# fpga-bank8.net
KiCad netlist of a schematic drawn in Altium Designer
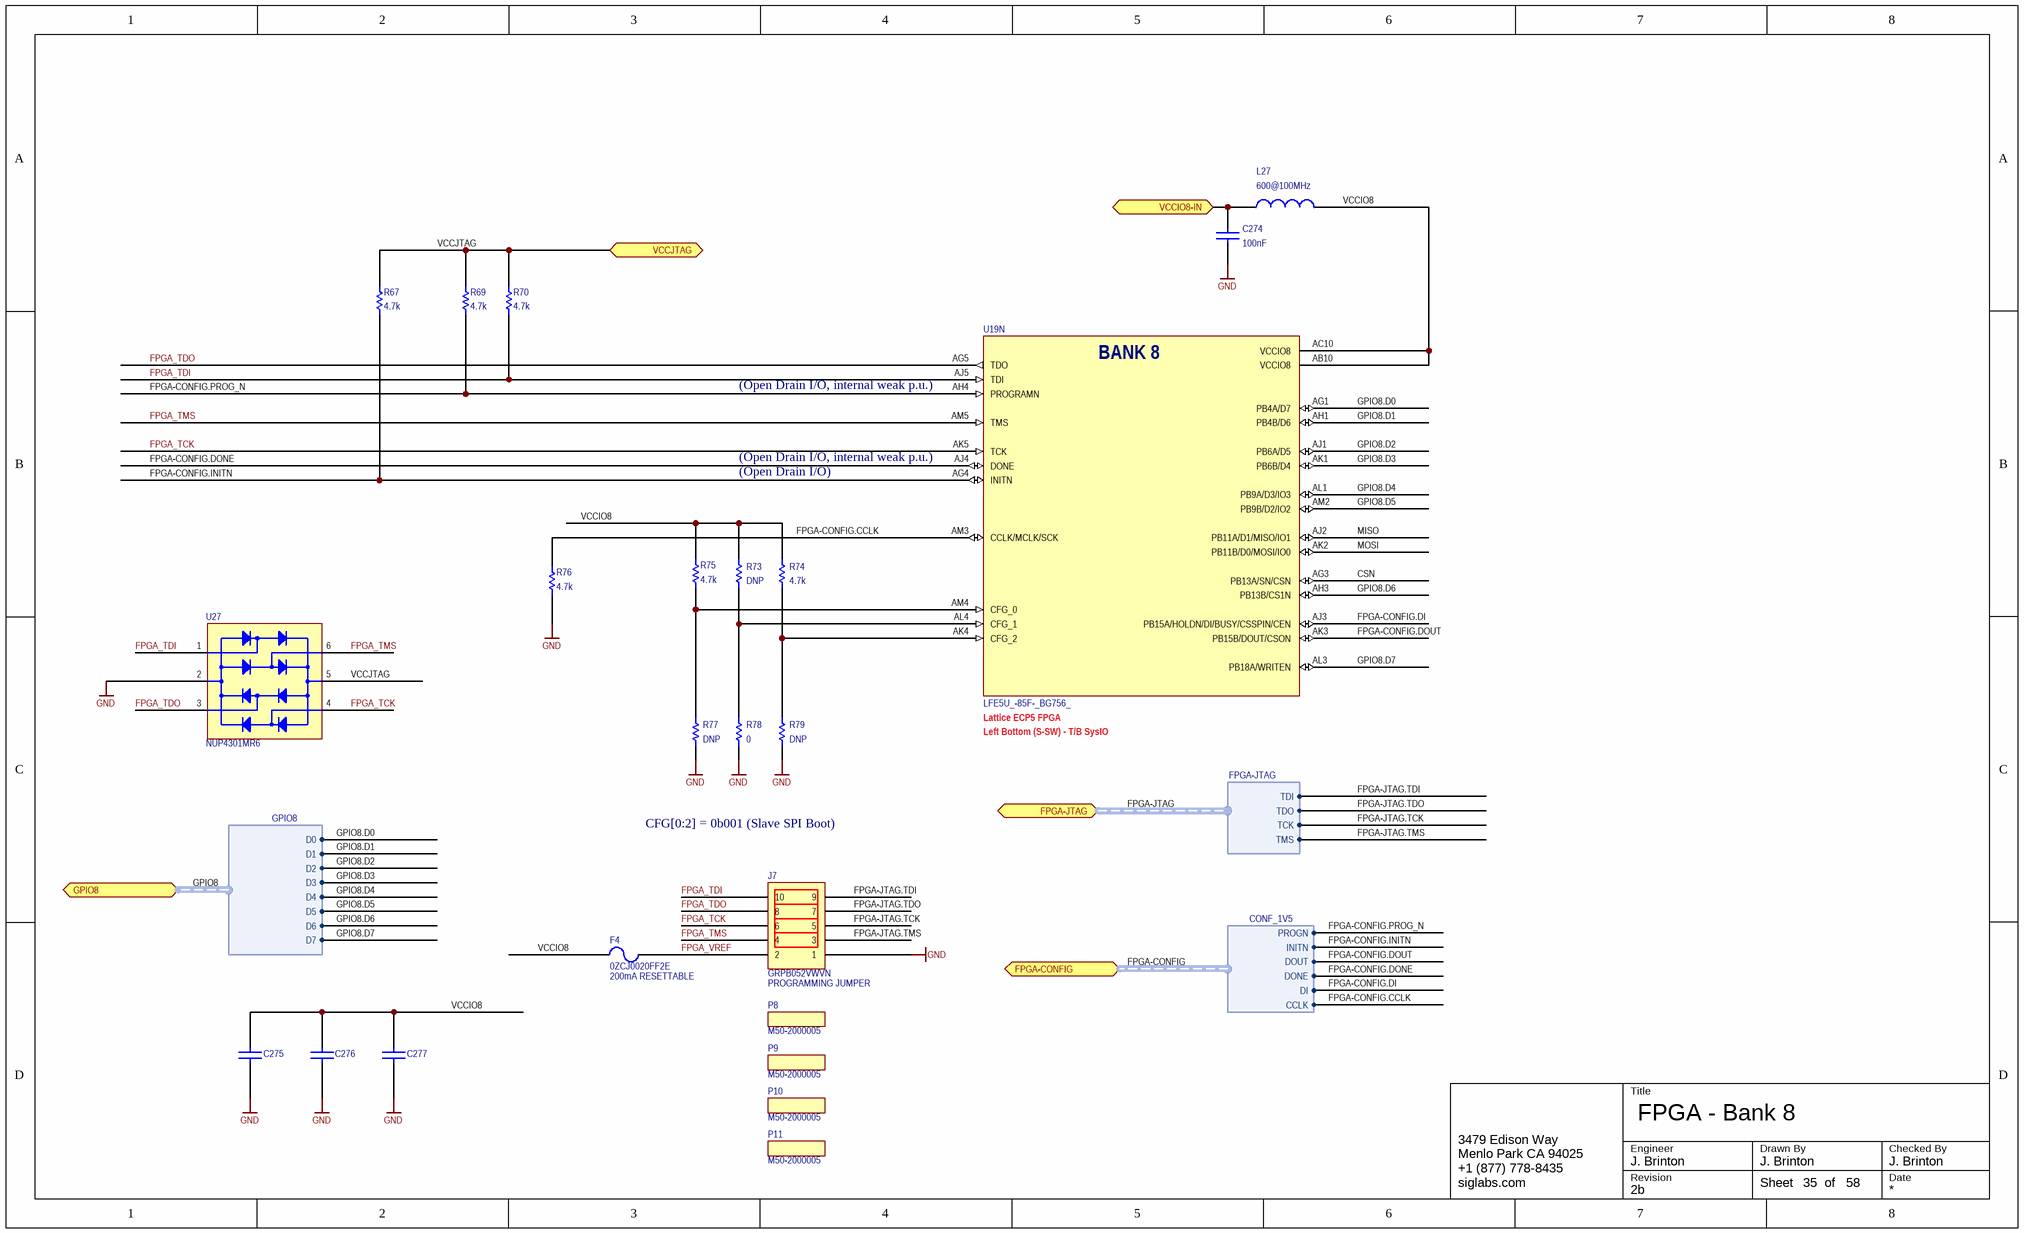
[diagram p0: fpga-bank8.SchDoc]

(export (version "E")
  (design (tool "Eeschema 10.0.6"))
  (components
    (comp (ref "C274")
      (value "100nF")
      (footprint "generic:CAPC1005X56N")
      (description "Ceramic Capacitor 100nF ±10% 16V X7R 0402")
      (fields (field (name "MANUFACTURER") "Murata") (field (name "TOLERANCE") "±10%"))
      (libsource (lib "murata") (part "GRM155R71A104KA01J"))
    )
    (comp (ref "C275")
      (value "GRM21BR71C225KA12L")
      (footprint "generic:CAPC1608X90N")
      (description "Ceramic Capacitor 2.2uF ±10% 10V X7R 0603")
      (fields (field (name "MANUFACTURER") "Murata") (field (name "TOLERANCE") "±10%"))
      (libsource (lib "murata") (part "GRM188R71A225KE15D"))
    )
    (comp (ref "C276")
      (value "GRM155R71C104KA88J")
      (footprint "generic:CAPC1005X56N")
      (description "Ceramic Capacitor 100nF ±10% 16V X7R 0402")
      (fields (field (name "MANUFACTURER") "Murata") (field (name "TOLERANCE") "±10%"))
      (libsource (lib "murata") (part "GRM155R71A104KA01J"))
    )
    (comp (ref "C277")
      (value "GRM155R71C104KA88J")
      (footprint "generic:CAPC1005X56N")
      (description "Ceramic Capacitor 100nF ±10% 16V X7R 0402")
      (fields (field (name "MANUFACTURER") "Murata") (field (name "TOLERANCE") "±10%"))
      (libsource (lib "murata") (part "GRM155R71A104KA01J"))
    )
    (comp (ref "F4")
      (value "0ZCJ0020FF2E")
      (footprint "generic:1206")
      (description "PTC Resettable Fuse, 0.2A, 30V, SMD 1206")
      (fields (field (name "MANUFACTURER") "Bell Fuse"))
      (libsource (lib "bel-fuse") (part "0ZCJ0020FF2E"))
    )
    (comp (ref "J7")
      (value "GRPB052VWVN")
      (footprint "sullins:GRPB052VWVN")
      (description "Male Header, 0.050\" Pitch, 2x5 Position")
      (fields (field (name "MANUFACTURER") "Sullins"))
      (libsource (lib "sullins") (part "GRPB052VWVN"))
    )
    (comp (ref "L27")
      (value "600@100MHz")
      (footprint "0402")
      (description "Ferrite Bead 600-Ohm @ 100MHz 900mA 0402")
      (fields (field (name "MANUFACTURER") "Murata") (field (name "TOLERANCE") "±25%"))
      (libsource (lib "Graviton") (part "IND 0402"))
    )
    (comp (ref "P8")
      (value "M50-2000005")
      (description "1.27mm Jumper Socket")
      (fields (field (name "MANUFACTURER") "Harwin"))
      (libsource (lib "harwin") (part "M50-1900005"))
    )
    (comp (ref "P9")
      (value "M50-2000005")
      (description "1.27mm Jumper Socket")
      (fields (field (name "MANUFACTURER") "Harwin"))
      (libsource (lib "harwin") (part "M50-1900005"))
    )
    (comp (ref "P10")
      (value "M50-2000005")
      (description "1.27mm Jumper Socket")
      (fields (field (name "MANUFACTURER") "Harwin"))
      (libsource (lib "harwin") (part "M50-1900005"))
    )
    (comp (ref "P11")
      (value "M50-2000005")
      (description "1.27mm Jumper Socket")
      (fields (field (name "MANUFACTURER") "Harwin"))
      (libsource (lib "harwin") (part "M50-1900005"))
    )
    (comp (ref "R67")
      (value "4.7k")
      (footprint "generic:0603")
      (description "Thick Film Resistor 4.7k ±1% 0603")
      (fields (field (name "TOLERANCE") "±1%") (field (name "MANUFACTURER") "Panasonic"))
      (libsource (lib "brinton") (part "RES"))
    )
    (comp (ref "R69")
      (value "4.7k")
      (footprint "generic:0603")
      (description "Thick Film Resistor 4.7k ±1% 0603")
      (fields (field (name "TOLERANCE") "±1%") (field (name "MANUFACTURER") "Panasonic"))
      (libsource (lib "brinton") (part "RES"))
    )
    (comp (ref "R70")
      (value "4.7k")
      (footprint "generic:0603")
      (description "Thick Film Resistor 4.7k ±1% 0603")
      (fields (field (name "TOLERANCE") "±1%") (field (name "MANUFACTURER") "Panasonic"))
      (libsource (lib "brinton") (part "RES"))
    )
    (comp (ref "R73")
      (value "ERJ3EKF4701V")
      (footprint "generic:0603")
      (description "Thick Film Resistor 4.7k ±1% 0603")
      (fields
        (field (name "TOLERANCE") "±1%")
        (field (name "MANUFACTURER") "Panasonic")
        (field (name "DO NOT PLACE") "DNP")
      )
      (libsource (lib "brinton") (part "RES"))
    )
    (comp (ref "R74")
      (value "4.7k")
      (footprint "generic:0603")
      (description "Thick Film Resistor 4.7k ±1% 0603")
      (fields (field (name "TOLERANCE") "±1%") (field (name "MANUFACTURER") "Panasonic"))
      (libsource (lib "brinton") (part "RES"))
    )
    (comp (ref "R75")
      (value "4.7k")
      (footprint "generic:0603")
      (description "Thick Film Resistor 4.7k ±1% 0603")
      (fields (field (name "TOLERANCE") "±1%") (field (name "MANUFACTURER") "Panasonic"))
      (libsource (lib "brinton") (part "RES"))
    )
    (comp (ref "R76")
      (value "4.7k")
      (footprint "generic:0603")
      (description "Thick Film Resistor 4.7k ±1% 0603")
      (fields (field (name "TOLERANCE") "±1%") (field (name "MANUFACTURER") "Panasonic"))
      (libsource (lib "brinton") (part "RES"))
    )
    (comp (ref "R77")
      (value "ERJ-3GEY0R00V")
      (footprint "generic:0603")
      (description "Thick Film Resistor Jumper 0603")
      (fields
        (field (name "TOLERANCE") "0")
        (field (name "MANUFACTURER") "Panasonic")
        (field (name "DO NOT PLACE") "DNP")
      )
      (libsource (lib "brinton") (part "RES"))
    )
    (comp (ref "R78")
      (value "0")
      (footprint "generic:0603")
      (description "Thick Film Resistor Jumper 0603")
      (fields (field (name "MANUFACTURER") "Panasonic") (field (name "Comment") "ERJ-3GEY0R00V"))
      (libsource (lib "brinton") (part "RES"))
    )
    (comp (ref "R79")
      (value "ERJ-3GEY0R00V")
      (footprint "generic:0603")
      (description "Thick Film Resistor Jumper 0603")
      (fields
        (field (name "TOLERANCE") "0")
        (field (name "MANUFACTURER") "Panasonic")
        (field (name "DO NOT PLACE") "DNP")
      )
      (libsource (lib "brinton") (part "RES"))
    )
    (comp (ref "U19")
      (value "LFE5U_-85F-_BG756_")
      (footprint "lattice:caBGA756")
      (description "ECP5 FPGA, 85k LUT, 756-caBGA")
      (fields (field (name "MANUFACTURER") "Lattice Semiconductor"))
      (libsource (lib "lattice") (part "LFE5U_-85F-_BG756_"))
    )
    (comp (ref "U27")
      (value "NUP4301MR6")
      (footprint "generic:SOT23-6")
      (description "4-Lane TVS Diode Array")
      (fields (field (name "MANUFACTURER") "On Semiconductor"))
      (libsource (lib "on_semi") (part "NUP4301MR6"))
    )
  )
  (nets
    (net (code "4") (name "/CSN") (class "Default")
      (node (ref "U19") (pin "AG3") (pinfunction "PB13A/SN/CSN_AG3") (pintype "bidirectional"))
    )
    (net (code "5") (name "/FPGA-CONFIG.CCLK") (class "Default")
      (node (ref "R76") (pin "2") (pinfunction "2_2") (pintype "passive"))
      (node (ref "U19") (pin "AM3") (pinfunction "CCLK/MCLK/SCK_AM3") (pintype "bidirectional"))
    )
    (net (code "6") (name "/FPGA-CONFIG.DI") (class "Default")
      (node (ref "U19") (pin "AJ3") (pinfunction "PB15A/HOLDN/DI/BUSY/CSSPIN/CEN_AJ3") (pintype "bidirectional"))
    )
    (net (code "7") (name "/FPGA-CONFIG.DONE") (class "Default")
      (node (ref "U19") (pin "AJ4") (pinfunction "DONE_AJ4") (pintype "bidirectional"))
    )
    (net (code "8") (name "/FPGA-CONFIG.DOUT") (class "Default")
      (node (ref "U19") (pin "AK3") (pinfunction "PB15B/DOUT/CSON_AK3") (pintype "bidirectional"))
    )
    (net (code "9") (name "/FPGA-CONFIG.INITN") (class "Default")
      (node (ref "R67") (pin "1") (pinfunction "1_1") (pintype "passive"))
      (node (ref "U19") (pin "AG4") (pinfunction "INITN_AG4") (pintype "bidirectional"))
    )
    (net (code "10") (name "/FPGA-CONFIG.PROG_N") (class "Default")
      (node (ref "R69") (pin "1") (pinfunction "1_1") (pintype "passive"))
      (node (ref "U19") (pin "AH4") (pinfunction "PROGRAMN_AH4") (pintype "input"))
    )
    (net (code "12") (name "/FPGA-JTAG.TCK") (class "Default")
      (node (ref "J7") (pin "5") (pinfunction "5_5") (pintype "passive"))
    )
    (net (code "13") (name "/FPGA-JTAG.TDI") (class "Default")
      (node (ref "J7") (pin "9") (pinfunction "9_9") (pintype "passive"))
    )
    (net (code "14") (name "/FPGA-JTAG.TDO") (class "Default")
      (node (ref "J7") (pin "7") (pinfunction "7_7") (pintype "passive"))
    )
    (net (code "15") (name "/FPGA-JTAG.TMS") (class "Default")
      (node (ref "J7") (pin "3") (pinfunction "3_3") (pintype "passive"))
    )
    (net (code "17") (name "/FPGA_TCK") (class "Default")
      (node (ref "J7") (pin "6") (pinfunction "6_6") (pintype "passive"))
      (node (ref "U19") (pin "AK5") (pinfunction "TCK_AK5") (pintype "input"))
      (node (ref "U27") (pin "4") (pinfunction "C_4") (pintype "passive"))
    )
    (net (code "18") (name "/FPGA_TDI") (class "Default")
      (node (ref "J7") (pin "10") (pinfunction "10_10") (pintype "passive"))
      (node (ref "R70") (pin "1") (pinfunction "1_1") (pintype "passive"))
      (node (ref "U19") (pin "AJ5") (pinfunction "TDI_AJ5") (pintype "input"))
      (node (ref "U27") (pin "1") (pinfunction "A_1") (pintype "passive"))
    )
    (net (code "19") (name "/FPGA_TDO") (class "Default")
      (node (ref "J7") (pin "8") (pinfunction "8_8") (pintype "passive"))
      (node (ref "U19") (pin "AG5") (pinfunction "TDO_AG5") (pintype "output"))
      (node (ref "U27") (pin "3") (pinfunction "B_3") (pintype "passive"))
    )
    (net (code "20") (name "/FPGA_TMS") (class "Default")
      (node (ref "J7") (pin "4") (pinfunction "4_4") (pintype "passive"))
      (node (ref "U19") (pin "AM5") (pinfunction "TMS_AM5") (pintype "input"))
      (node (ref "U27") (pin "6") (pinfunction "D_6") (pintype "passive"))
    )
    (net (code "21") (name "/FPGA_VREF") (class "Default")
      (node (ref "F4") (pin "2") (pinfunction "2_2") (pintype "passive"))
      (node (ref "J7") (pin "2") (pinfunction "2_2") (pintype "passive"))
    )
    (net (code "22") (name "/GPIO8.D0") (class "Default")
      (node (ref "U19") (pin "AG1") (pinfunction "PB4A/D7_AG1") (pintype "bidirectional"))
    )
    (net (code "23") (name "/GPIO8.D1") (class "Default")
      (node (ref "U19") (pin "AH1") (pinfunction "PB4B/D6_AH1") (pintype "bidirectional"))
    )
    (net (code "24") (name "/GPIO8.D2") (class "Default")
      (node (ref "U19") (pin "AJ1") (pinfunction "PB6A/D5_AJ1") (pintype "bidirectional"))
    )
    (net (code "25") (name "/GPIO8.D3") (class "Default")
      (node (ref "U19") (pin "AK1") (pinfunction "PB6B/D4_AK1") (pintype "bidirectional"))
    )
    (net (code "26") (name "/GPIO8.D4") (class "Default")
      (node (ref "U19") (pin "AL1") (pinfunction "PB9A/D3/IO3_AL1") (pintype "bidirectional"))
    )
    (net (code "27") (name "/GPIO8.D5") (class "Default")
      (node (ref "U19") (pin "AM2") (pinfunction "PB9B/D2/IO2_AM2") (pintype "bidirectional"))
    )
    (net (code "28") (name "/GPIO8.D6") (class "Default")
      (node (ref "U19") (pin "AH3") (pinfunction "PB13B/CS1N_AH3") (pintype "bidirectional"))
    )
    (net (code "29") (name "/GPIO8.D7") (class "Default")
      (node (ref "U19") (pin "AL3") (pinfunction "PB18A/WRITEN_AL3") (pintype "bidirectional"))
    )
    (net (code "31") (name "/MISO") (class "Default")
      (node (ref "U19") (pin "AJ2") (pinfunction "PB11A/D1/MISO/IO1_AJ2") (pintype "bidirectional"))
    )
    (net (code "32") (name "/MOSI") (class "Default")
      (node (ref "U19") (pin "AK2") (pinfunction "PB11B/D0/MOSI/IO0_AK2") (pintype "bidirectional"))
    )
    (net (code "33") (name "/VCCIO8") (class "Default")
      (node (ref "C275") (pin "2") (pinfunction "2_2") (pintype "passive"))
      (node (ref "C276") (pin "2") (pinfunction "2_2") (pintype "passive"))
      (node (ref "C277") (pin "2") (pinfunction "2_2") (pintype "passive"))
      (node (ref "F4") (pin "1") (pinfunction "1_1") (pintype "passive"))
      (node (ref "L27") (pin "1") (pinfunction "1_1") (pintype "passive"))
      (node (ref "R73") (pin "2") (pinfunction "2_2") (pintype "passive"))
      (node (ref "R74") (pin "2") (pinfunction "2_2") (pintype "passive"))
      (node (ref "R75") (pin "2") (pinfunction "2_2") (pintype "passive"))
      (node (ref "U19") (pin "AB10") (pinfunction "VCCIO8_AB10") (pintype "power_in"))
      (node (ref "U19") (pin "AC10") (pinfunction "VCCIO8_AC10") (pintype "power_in"))
    )
    (net (code "34") (name "/VCCIO8-IN") (class "Default")
      (node (ref "C274") (pin "2") (pinfunction "2_2") (pintype "passive"))
      (node (ref "L27") (pin "2") (pinfunction "2_2") (pintype "passive"))
    )
    (net (code "35") (name "/VCCJTAG") (class "Default")
      (node (ref "R67") (pin "2") (pinfunction "2_2") (pintype "passive"))
      (node (ref "R69") (pin "2") (pinfunction "2_2") (pintype "passive"))
      (node (ref "R70") (pin "2") (pinfunction "2_2") (pintype "passive"))
      (node (ref "U27") (pin "5") (pinfunction "VP_5") (pintype "passive"))
    )
    (net (code "36") (name "GND") (class "Default")
      (node (ref "C274") (pin "1") (pinfunction "1_1") (pintype "passive"))
      (node (ref "C275") (pin "1") (pinfunction "1_1") (pintype "passive"))
      (node (ref "C276") (pin "1") (pinfunction "1_1") (pintype "passive"))
      (node (ref "C277") (pin "1") (pinfunction "1_1") (pintype "passive"))
      (node (ref "J7") (pin "1") (pinfunction "1_1") (pintype "passive"))
      (node (ref "R76") (pin "1") (pinfunction "1_1") (pintype "passive"))
      (node (ref "R77") (pin "1") (pinfunction "1_1") (pintype "passive"))
      (node (ref "R78") (pin "1") (pinfunction "1_1") (pintype "passive"))
      (node (ref "R79") (pin "1") (pinfunction "1_1") (pintype "passive"))
      (node (ref "U27") (pin "2") (pinfunction "VN_2") (pintype "passive"))
    )
    (net (code "37") (name "Net-(U19N-CFG_0)") (class "Default")
      (node (ref "R75") (pin "1") (pinfunction "1_1") (pintype "passive"))
      (node (ref "R77") (pin "2") (pinfunction "2_2") (pintype "passive"))
      (node (ref "U19") (pin "AM4") (pinfunction "CFG_0_AM4") (pintype "input"))
    )
    (net (code "38") (name "Net-(U19N-CFG_1)") (class "Default")
      (node (ref "R73") (pin "1") (pinfunction "1_1") (pintype "passive"))
      (node (ref "R78") (pin "2") (pinfunction "2_2") (pintype "passive"))
      (node (ref "U19") (pin "AL4") (pinfunction "CFG_1_AL4") (pintype "input"))
    )
    (net (code "39") (name "Net-(U19N-CFG_2)") (class "Default")
      (node (ref "R74") (pin "1") (pinfunction "1_1") (pintype "passive"))
      (node (ref "R79") (pin "2") (pinfunction "2_2") (pintype "passive"))
      (node (ref "U19") (pin "AK4") (pinfunction "CFG_2_AK4") (pintype "input"))
    )
  )
)
